# old_line_kick.net
KiCad netlist of a schematic drawn in EAGLE
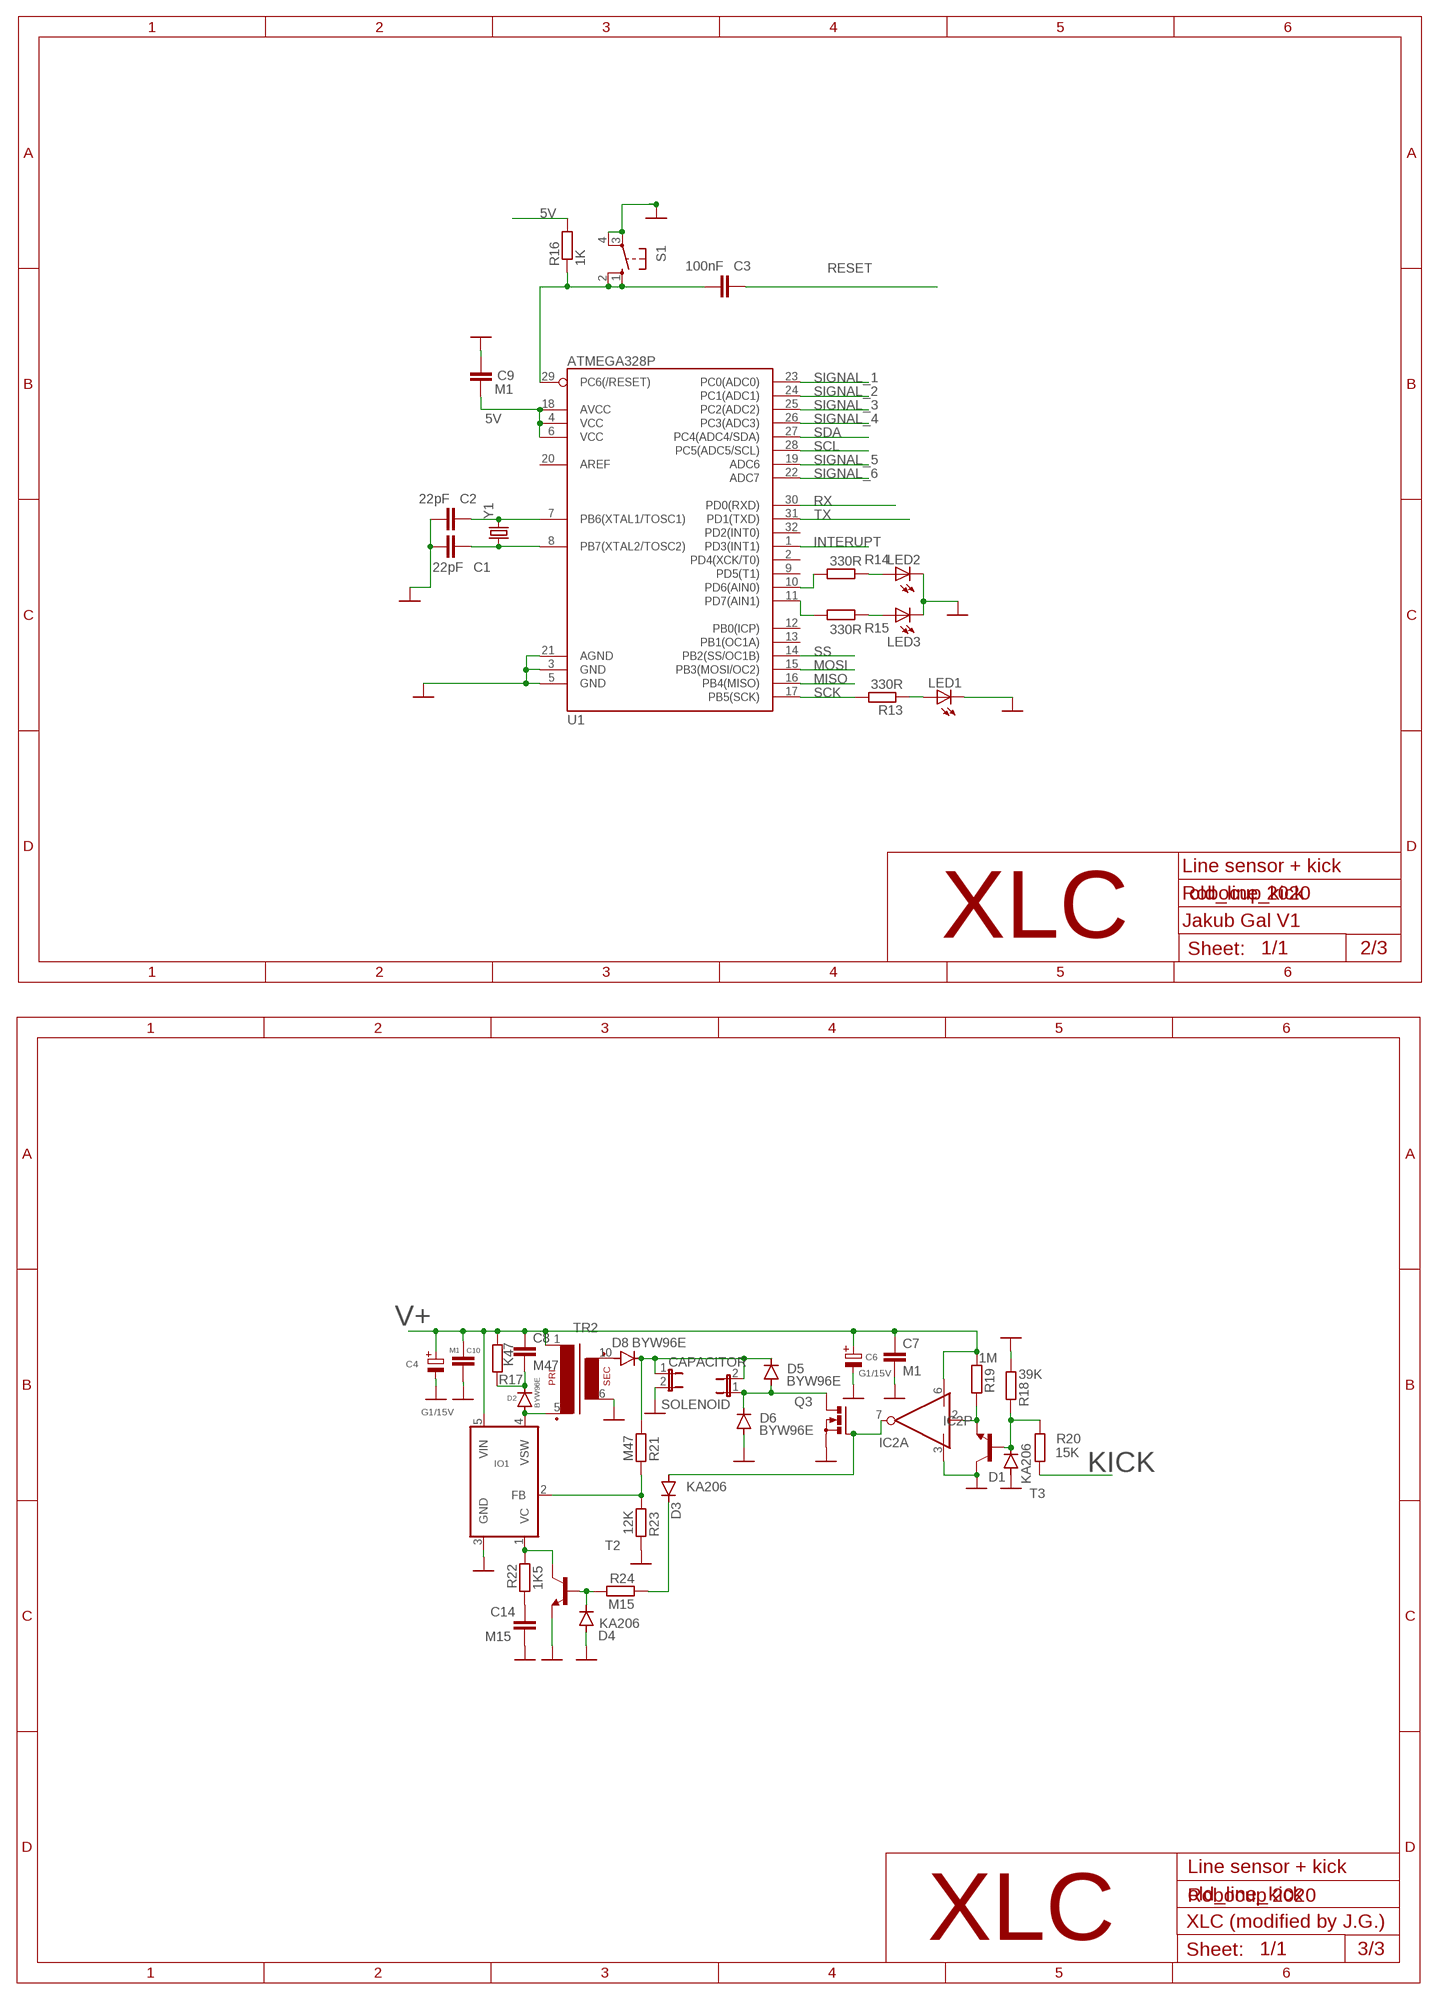
[diagram p0: schematic, sheet 1, part 1 of 2]
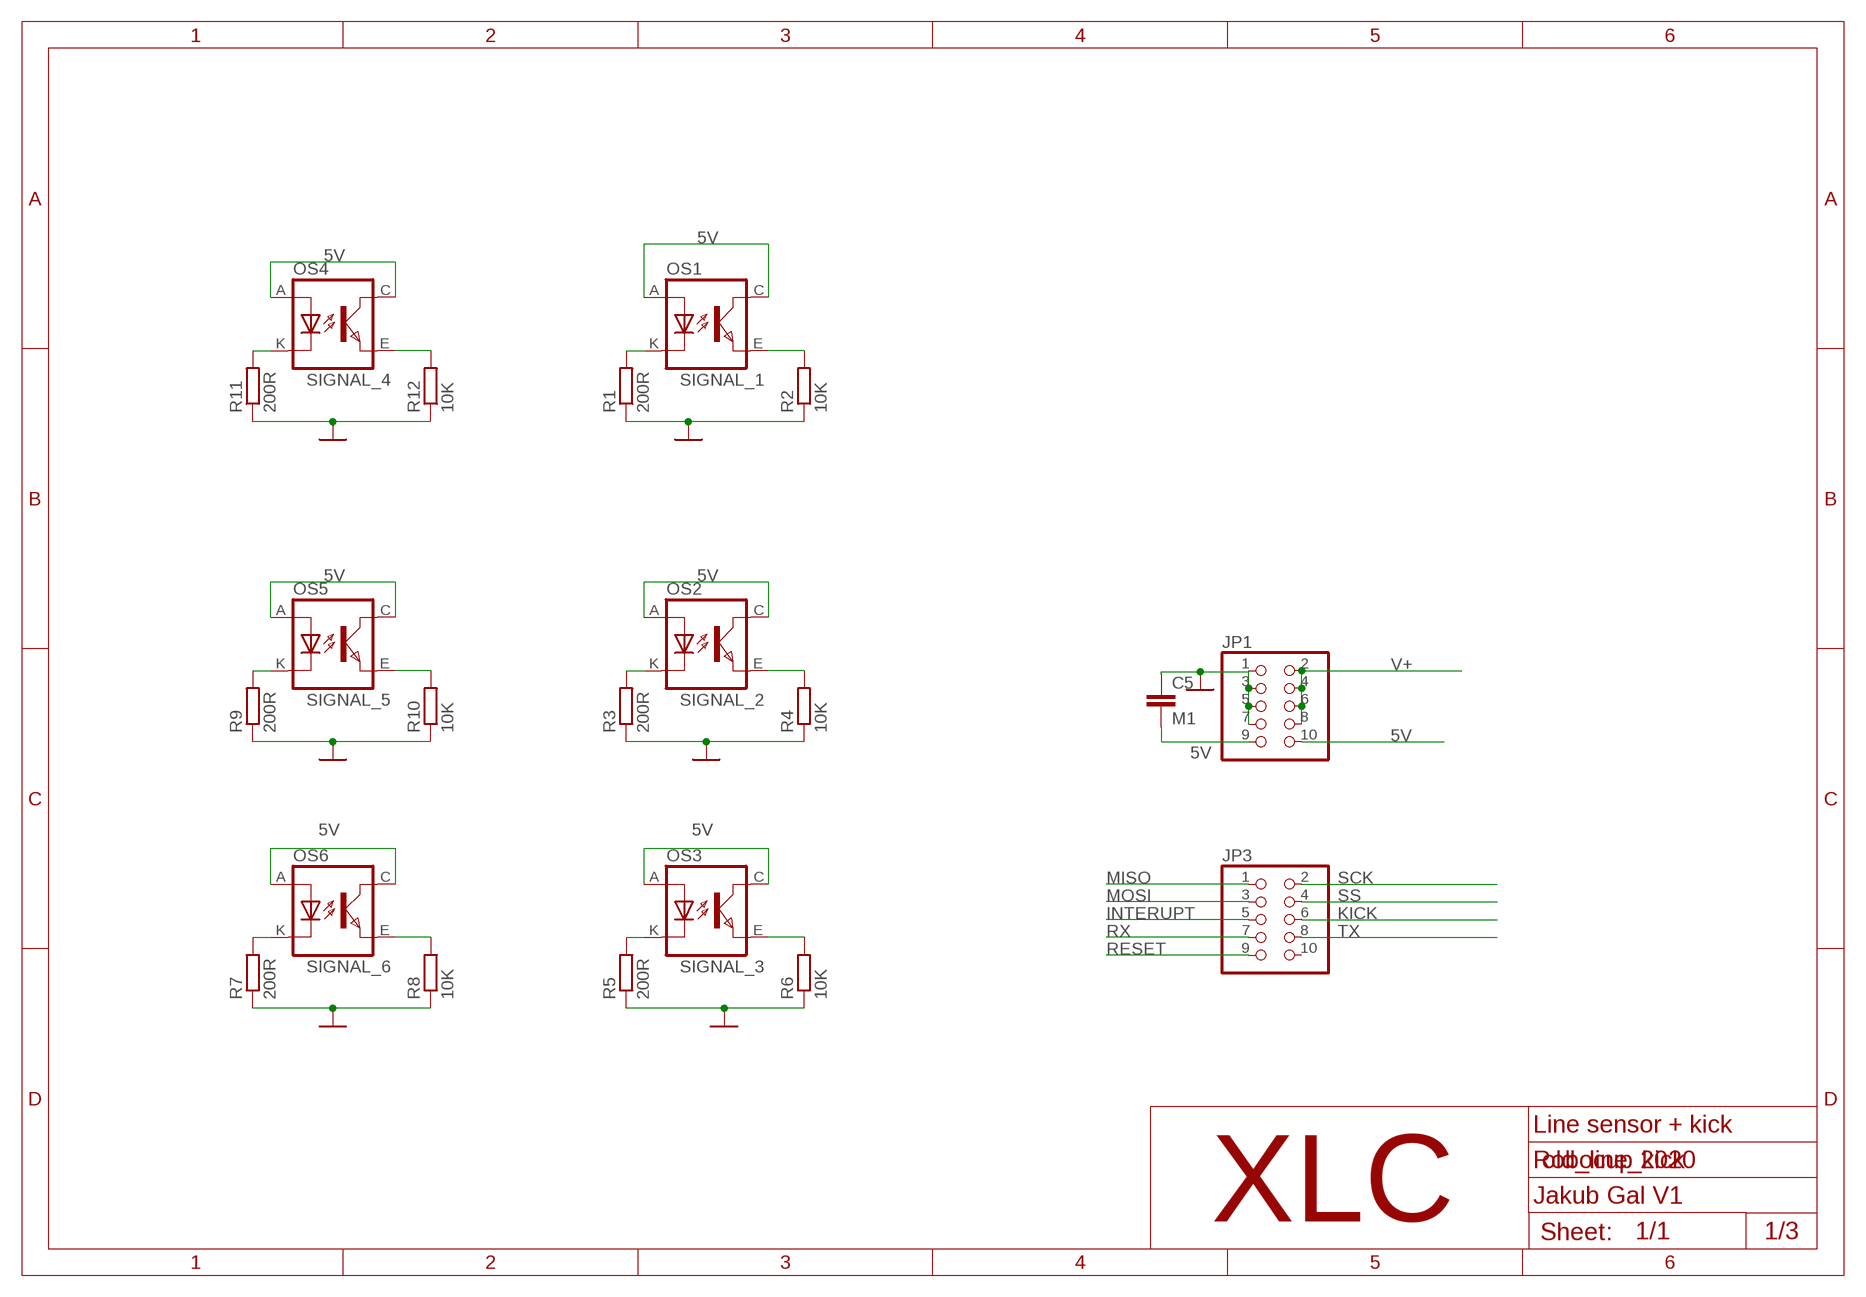
[diagram p1: schematic, sheet 1, part 2 of 2]

(export (version "E")
  (design (tool "Eeschema 10.0.6"))
  (components
    (comp (ref "C1")
      (value "22pF")
      (footprint "eagle-import:C0603")
      (libsource (lib "eagle-import") (part "rcl@1_C-EUC0603"))
    )
    (comp (ref "C2")
      (value "22pF")
      (footprint "eagle-import:C0603")
      (libsource (lib "eagle-import") (part "rcl@1_C-EUC0603"))
    )
    (comp (ref "C3")
      (value "100nF")
      (footprint "eagle-import:C0603")
      (libsource (lib "eagle-import") (part "rcl@1_C-EUC0603"))
    )
    (comp (ref "C4")
      (value "G1/15V")
      (footprint "eagle-import:E-2,5_7-RAD")
      (libsource (lib "eagle-import") (part "KOND-ELEKT-2,5/7"))
    )
    (comp (ref "C5")
      (value "M1")
      (footprint "eagle-import:C0603")
      (libsource (lib "eagle-import") (part "C-EUC0603"))
    )
    (comp (ref "C6")
      (value "G1/15V")
      (footprint "eagle-import:E-2,5_7-RAD")
      (libsource (lib "eagle-import") (part "KOND-ELEKT-2,5/7"))
    )
    (comp (ref "C7")
      (value "M1")
      (footprint "eagle-import:C0805K")
      (libsource (lib "eagle-import") (part "resistor_C-EUC0805K"))
    )
    (comp (ref "C8")
      (value "M47")
      (footprint "eagle-import:C1206K")
      (libsource (lib "eagle-import") (part "C-EUC1206K"))
    )
    (comp (ref "C9")
      (value "M1")
      (footprint "eagle-import:C0603")
      (libsource (lib "eagle-import") (part "rcl@1_C-EUC0603"))
    )
    (comp (ref "C10")
      (value "M1")
      (footprint "eagle-import:C0805K")
      (libsource (lib "eagle-import") (part "resistor_C-EUC0805K"))
    )
    (comp (ref "C14")
      (value "M15")
      (footprint "eagle-import:C0805K")
      (libsource (lib "eagle-import") (part "resistor_C-EUC0805K"))
    )
    (comp (ref "CAPACITOR")
      (value "JP1E")
      (footprint "eagle-import:JP1")
      (libsource (lib "eagle-import") (part "JP1E"))
    )
    (comp (ref "D1")
      (value "KA206")
      (footprint "eagle-import:D-7.5")
      (libsource (lib "eagle-import") (part "DIODE-D-7.5"))
    )
    (comp (ref "D2")
      (value "BYW96E")
      (footprint "eagle-import:SOD64-10")
      (libsource (lib "eagle-import") (part "BYW96"))
    )
    (comp (ref "D3")
      (value "KA206")
      (footprint "eagle-import:D-7.5")
      (libsource (lib "eagle-import") (part "DIODE-D-7.5"))
    )
    (comp (ref "D4")
      (value "KA206")
      (footprint "eagle-import:D-7.5")
      (libsource (lib "eagle-import") (part "DIODE-D-7.5"))
    )
    (comp (ref "D5")
      (value "BYW96E")
      (footprint "eagle-import:SOD64-10")
      (libsource (lib "eagle-import") (part "BYW96"))
    )
    (comp (ref "D6")
      (value "BYW96E")
      (footprint "eagle-import:SOD64-10")
      (libsource (lib "eagle-import") (part "BYW96"))
    )
    (comp (ref "D8")
      (value "BYW96E")
      (footprint "eagle-import:SOD64-10")
      (libsource (lib "eagle-import") (part "BYW96"))
    )
    (comp (ref "IC2")
      (value "MIC4423BM")
      (footprint "eagle-import:SO08")
      (libsource (lib "eagle-import") (part "MIC4423BM"))
    )
    (comp (ref "IO1")
      (value "LT1071V")
      (footprint "eagle-import:TO220-5P")
      (libsource (lib "eagle-import") (part "LT1071V"))
    )
    (comp (ref "JP1")
      (value "PINHD-2X5IDC")
      (footprint "eagle-import:2X05_IDC")
      (libsource (lib "eagle-import") (part "PINHD-2X5IDC"))
    )
    (comp (ref "JP3")
      (value "PINHD-2X5IDC")
      (footprint "eagle-import:2X05_IDC")
      (libsource (lib "eagle-import") (part "PINHD-2X5IDC"))
    )
    (comp (ref "LED1")
      (value "LEDCHIPLED_0603")
      (footprint "eagle-import:CHIPLED_0603")
      (libsource (lib "eagle-import") (part "LEDCHIPLED_0603"))
    )
    (comp (ref "LED2")
      (value "LEDCHIPLED_0603")
      (footprint "eagle-import:CHIPLED_0603")
      (libsource (lib "eagle-import") (part "LEDCHIPLED_0603"))
    )
    (comp (ref "LED3")
      (value "LEDCHIPLED_0603")
      (footprint "eagle-import:CHIPLED_0603")
      (libsource (lib "eagle-import") (part "LEDCHIPLED_0603"))
    )
    (comp (ref "OS1")
      (value "TCRT5000")
      (footprint "eagle-import:TCRT5000")
      (libsource (lib "eagle-import") (part "TCRT5000"))
    )
    (comp (ref "OS2")
      (value "TCRT5000")
      (footprint "eagle-import:TCRT5000")
      (libsource (lib "eagle-import") (part "TCRT5000"))
    )
    (comp (ref "OS3")
      (value "TCRT5000")
      (footprint "eagle-import:TCRT5000")
      (libsource (lib "eagle-import") (part "TCRT5000"))
    )
    (comp (ref "OS4")
      (value "TCRT5000")
      (footprint "eagle-import:TCRT5000")
      (fields (field (name "SPICEPREFIX") "O"))
      (libsource (lib "eagle-import") (part "TCRT5000"))
    )
    (comp (ref "OS5")
      (value "TCRT5000")
      (footprint "eagle-import:TCRT5000")
      (libsource (lib "eagle-import") (part "TCRT5000"))
    )
    (comp (ref "OS6")
      (value "TCRT5000")
      (footprint "eagle-import:TCRT5000")
      (fields (field (name "SPICEPREFIX") "O"))
      (libsource (lib "eagle-import") (part "TCRT5000"))
    )
    (comp (ref "Q3")
      (value "PMOSFET_NTO220BV")
      (footprint "eagle-import:TO220BV")
      (libsource (lib "eagle-import") (part "PMOSFET_NTO220BV"))
    )
    (comp (ref "R1")
      (value "200R")
      (footprint "eagle-import:R0603")
      (libsource (lib "eagle-import") (part "R-EU_R0603"))
    )
    (comp (ref "R2")
      (value "10K")
      (footprint "eagle-import:R0603")
      (libsource (lib "eagle-import") (part "R-EU_R0603"))
    )
    (comp (ref "R3")
      (value "200R")
      (footprint "eagle-import:R0603")
      (libsource (lib "eagle-import") (part "R-EU_R0603"))
    )
    (comp (ref "R4")
      (value "10K")
      (footprint "eagle-import:R0603")
      (libsource (lib "eagle-import") (part "R-EU_R0603"))
    )
    (comp (ref "R5")
      (value "200R")
      (footprint "eagle-import:R0603")
      (libsource (lib "eagle-import") (part "R-EU_R0603"))
    )
    (comp (ref "R6")
      (value "10K")
      (footprint "eagle-import:R0603")
      (libsource (lib "eagle-import") (part "R-EU_R0603"))
    )
    (comp (ref "R7")
      (value "200R")
      (footprint "eagle-import:R0603")
      (libsource (lib "eagle-import") (part "R-EU_R0603"))
    )
    (comp (ref "R8")
      (value "10K")
      (footprint "eagle-import:R0603")
      (libsource (lib "eagle-import") (part "R-EU_R0603"))
    )
    (comp (ref "R9")
      (value "200R")
      (footprint "eagle-import:R0603")
      (libsource (lib "eagle-import") (part "R-EU_R0603"))
    )
    (comp (ref "R10")
      (value "10K")
      (footprint "eagle-import:R0603")
      (libsource (lib "eagle-import") (part "R-EU_R0603"))
    )
    (comp (ref "R11")
      (value "200R")
      (footprint "eagle-import:R0603")
      (libsource (lib "eagle-import") (part "R-EU_R0603"))
    )
    (comp (ref "R12")
      (value "10K")
      (footprint "eagle-import:R0603")
      (libsource (lib "eagle-import") (part "R-EU_R0603"))
    )
    (comp (ref "R13")
      (value "330R")
      (footprint "eagle-import:R0603")
      (libsource (lib "eagle-import") (part "R-EU_R0603"))
    )
    (comp (ref "R14")
      (value "330R")
      (footprint "eagle-import:R0603")
      (libsource (lib "eagle-import") (part "R-EU_R0603"))
    )
    (comp (ref "R15")
      (value "330R")
      (footprint "eagle-import:R0603")
      (libsource (lib "eagle-import") (part "R-EU_R0603"))
    )
    (comp (ref "R16")
      (value "1K")
      (footprint "eagle-import:R0603")
      (libsource (lib "eagle-import") (part "R-EU_R0603"))
    )
    (comp (ref "R17")
      (value "K47")
      (footprint "eagle-import:R0603")
      (libsource (lib "eagle-import") (part "resistor_R-EU_R0603"))
    )
    (comp (ref "R18")
      (value "39K")
      (footprint "eagle-import:R0603")
      (libsource (lib "eagle-import") (part "resistor_R-EU_R0603"))
    )
    (comp (ref "R19")
      (value "1M")
      (footprint "eagle-import:R0603")
      (libsource (lib "eagle-import") (part "resistor_R-EU_R0603"))
    )
    (comp (ref "R20")
      (value "15K")
      (footprint "eagle-import:R0603")
      (libsource (lib "eagle-import") (part "resistor_R-EU_R0603"))
    )
    (comp (ref "R21")
      (value "M47")
      (footprint "eagle-import:R0603")
      (libsource (lib "eagle-import") (part "resistor_R-EU_R0603"))
    )
    (comp (ref "R22")
      (value "1K5")
      (footprint "eagle-import:R0603")
      (libsource (lib "eagle-import") (part "resistor_R-EU_R0603"))
    )
    (comp (ref "R23")
      (value "12K")
      (footprint "eagle-import:R0603")
      (libsource (lib "eagle-import") (part "resistor_R-EU_R0603"))
    )
    (comp (ref "R24")
      (value "M15")
      (footprint "eagle-import:R0603")
      (libsource (lib "eagle-import") (part "resistor_R-EU_R0603"))
    )
    (comp (ref "S1")
      (value "10-XX")
      (footprint "eagle-import:B3F-10XX")
      (fields (field (name "MPN") "B3F-1000"))
      (libsource (lib "eagle-import") (part "10-XX"))
    )
    (comp (ref "SOLENOID")
      (value "JP1E")
      (footprint "eagle-import:JP1")
      (libsource (lib "eagle-import") (part "JP1E"))
    )
    (comp (ref "T2")
      (value "-NPN-SC59-BEC")
      (footprint "eagle-import:SC59-BEC")
      (libsource (lib "eagle-import") (part "-NPN-SC59-BEC"))
    )
    (comp (ref "T3")
      (value "-NPN-SC59-BEC")
      (footprint "eagle-import:SC59-BEC")
      (libsource (lib "eagle-import") (part "-NPN-SC59-BEC"))
    )
    (comp (ref "TR2")
      (value "TRAFO-E10-R\"\"")
      (footprint "eagle-import:TRAFO-EE17X20")
      (libsource (lib "eagle-import") (part "TRAFO-E10-R{dblquote}{dblquote}"))
    )
    (comp (ref "U1")
      (value "ATMEGA328P")
      (footprint "eagle-import:TQFP32-08")
      (libsource (lib "eagle-import") (part "ATMEGA328_SMT"))
    )
    (comp (ref "Y1")
      (value "CRYSTALHC49US")
      (footprint "eagle-import:HC49US")
      (libsource (lib "eagle-import") (part "CRYSTALHC49US"))
    )
  )
  (nets
    (net (code "1") (name "/5V") (class "Default")
      (node (ref "C5") (pin "2") (pinfunction "2_2") (pintype "passive"))
      (node (ref "C9") (pin "1") (pinfunction "1_1") (pintype "passive"))
      (node (ref "JP1") (pin "10") (pinfunction "10_10") (pintype "passive"))
      (node (ref "JP1") (pin "9") (pinfunction "9_9") (pintype "passive"))
      (node (ref "OS1") (pin "A") (pinfunction "ANODE_A") (pintype "passive"))
      (node (ref "OS1") (pin "C") (pinfunction "COLLECTOR_C") (pintype "passive"))
      (node (ref "OS2") (pin "A") (pinfunction "ANODE_A") (pintype "passive"))
      (node (ref "OS2") (pin "C") (pinfunction "COLLECTOR_C") (pintype "passive"))
      (node (ref "OS3") (pin "A") (pinfunction "ANODE_A") (pintype "passive"))
      (node (ref "OS3") (pin "C") (pinfunction "COLLECTOR_C") (pintype "passive"))
      (node (ref "OS4") (pin "A") (pinfunction "ANODE_A") (pintype "passive"))
      (node (ref "OS4") (pin "C") (pinfunction "COLLECTOR_C") (pintype "passive"))
      (node (ref "OS5") (pin "A") (pinfunction "ANODE_A") (pintype "passive"))
      (node (ref "OS5") (pin "C") (pinfunction "COLLECTOR_C") (pintype "passive"))
      (node (ref "OS6") (pin "A") (pinfunction "ANODE_A") (pintype "passive"))
      (node (ref "OS6") (pin "C") (pinfunction "COLLECTOR_C") (pintype "passive"))
      (node (ref "R16") (pin "2") (pinfunction "2_2") (pintype "passive"))
      (node (ref "U1") (pin "18") (pinfunction "AVCC_18") (pintype "bidirectional"))
      (node (ref "U1") (pin "4") (pinfunction "VCC_4") (pintype "bidirectional"))
      (node (ref "U1") (pin "6") (pinfunction "VCC_6") (pintype "bidirectional"))
    )
    (net (code "2") (name "/INTERUPT") (class "Default")
      (node (ref "JP3") (pin "5") (pinfunction "5_5") (pintype "passive"))
      (node (ref "U1") (pin "1") (pinfunction "PD3(INT1)_1") (pintype "bidirectional"))
    )
    (net (code "3") (name "/KICK") (class "Default")
      (node (ref "JP3") (pin "6") (pinfunction "6_6") (pintype "passive"))
      (node (ref "R20") (pin "1") (pinfunction "1_1") (pintype "passive"))
    )
    (net (code "4") (name "/MISO") (class "Default")
      (node (ref "JP3") (pin "1") (pinfunction "1_1") (pintype "passive"))
      (node (ref "U1") (pin "16") (pinfunction "PB4(MISO)_16") (pintype "bidirectional"))
    )
    (net (code "5") (name "/MOSI") (class "Default")
      (node (ref "JP3") (pin "3") (pinfunction "3_3") (pintype "passive"))
      (node (ref "U1") (pin "15") (pinfunction "PB3(MOSI/OC2)_15") (pintype "bidirectional"))
    )
    (net (code "6") (name "/RESET") (class "Default")
      (node (ref "C3") (pin "2") (pinfunction "2_2") (pintype "passive"))
      (node (ref "JP3") (pin "9") (pinfunction "9_9") (pintype "passive"))
    )
    (net (code "7") (name "/RX") (class "Default")
      (node (ref "JP3") (pin "7") (pinfunction "7_7") (pintype "passive"))
      (node (ref "U1") (pin "30") (pinfunction "PD0(RXD)_30") (pintype "bidirectional"))
    )
    (net (code "8") (name "/SCK") (class "Default")
      (node (ref "JP3") (pin "2") (pinfunction "2_2") (pintype "passive"))
      (node (ref "R13") (pin "2") (pinfunction "2_2") (pintype "passive"))
      (node (ref "U1") (pin "17") (pinfunction "PB5(SCK)_17") (pintype "bidirectional"))
    )
    (net (code "9") (name "/SCL") (class "Default")
      (node (ref "U1") (pin "28") (pinfunction "PC5(ADC5/SCL)_28") (pintype "bidirectional"))
    )
    (net (code "10") (name "/SDA") (class "Default")
      (node (ref "U1") (pin "27") (pinfunction "PC4(ADC4/SDA)_27") (pintype "bidirectional"))
    )
    (net (code "11") (name "/SIGNAL_1") (class "Default")
      (node (ref "OS1") (pin "E") (pinfunction "EMITTER_E") (pintype "passive"))
      (node (ref "R2") (pin "2") (pinfunction "2_2") (pintype "passive"))
      (node (ref "U1") (pin "23") (pinfunction "PC0(ADC0)_23") (pintype "bidirectional"))
    )
    (net (code "12") (name "/SIGNAL_2") (class "Default")
      (node (ref "OS2") (pin "E") (pinfunction "EMITTER_E") (pintype "passive"))
      (node (ref "R4") (pin "2") (pinfunction "2_2") (pintype "passive"))
      (node (ref "U1") (pin "24") (pinfunction "PC1(ADC1)_24") (pintype "bidirectional"))
    )
    (net (code "13") (name "/SIGNAL_3") (class "Default")
      (node (ref "OS3") (pin "E") (pinfunction "EMITTER_E") (pintype "passive"))
      (node (ref "R6") (pin "2") (pinfunction "2_2") (pintype "passive"))
      (node (ref "U1") (pin "25") (pinfunction "PC2(ADC2)_25") (pintype "bidirectional"))
    )
    (net (code "14") (name "/SIGNAL_4") (class "Default")
      (node (ref "OS4") (pin "E") (pinfunction "EMITTER_E") (pintype "passive"))
      (node (ref "R12") (pin "2") (pinfunction "2_2") (pintype "passive"))
      (node (ref "U1") (pin "26") (pinfunction "PC3(ADC3)_26") (pintype "bidirectional"))
    )
    (net (code "15") (name "/SIGNAL_5") (class "Default")
      (node (ref "OS5") (pin "E") (pinfunction "EMITTER_E") (pintype "passive"))
      (node (ref "R10") (pin "2") (pinfunction "2_2") (pintype "passive"))
      (node (ref "U1") (pin "19") (pinfunction "ADC6_19") (pintype "bidirectional"))
    )
    (net (code "16") (name "/SIGNAL_6") (class "Default")
      (node (ref "OS6") (pin "E") (pinfunction "EMITTER_E") (pintype "passive"))
      (node (ref "R8") (pin "2") (pinfunction "2_2") (pintype "passive"))
      (node (ref "U1") (pin "22") (pinfunction "ADC7_22") (pintype "bidirectional"))
    )
    (net (code "17") (name "/SS") (class "Default")
      (node (ref "JP3") (pin "4") (pinfunction "4_4") (pintype "passive"))
      (node (ref "U1") (pin "14") (pinfunction "PB2(SS/OC1B)_14") (pintype "bidirectional"))
    )
    (net (code "18") (name "/TX") (class "Default")
      (node (ref "JP3") (pin "8") (pinfunction "8_8") (pintype "passive"))
      (node (ref "U1") (pin "31") (pinfunction "PD1(TXD)_31") (pintype "bidirectional"))
    )
    (net (code "19") (name "/V+") (class "Default")
      (node (ref "C10") (pin "1") (pinfunction "1_1") (pintype "passive"))
      (node (ref "C4") (pin "+") (pinfunction "+_+") (pintype "passive"))
      (node (ref "C6") (pin "+") (pinfunction "+_+") (pintype "passive"))
      (node (ref "C7") (pin "1") (pinfunction "1_1") (pintype "passive"))
      (node (ref "C8") (pin "1") (pinfunction "1_1") (pintype "passive"))
      (node (ref "IC2") (pin "6") (pinfunction "V+_6") (pintype "power_in"))
      (node (ref "IO1") (pin "5") (pinfunction "VIN_5") (pintype "power_in"))
      (node (ref "JP1") (pin "2") (pinfunction "2_2") (pintype "passive"))
      (node (ref "JP1") (pin "4") (pinfunction "4_4") (pintype "passive"))
      (node (ref "JP1") (pin "6") (pinfunction "6_6") (pintype "passive"))
      (node (ref "JP1") (pin "8") (pinfunction "8_8") (pintype "passive"))
      (node (ref "R17") (pin "1") (pinfunction "1_1") (pintype "passive"))
      (node (ref "R19") (pin "2") (pinfunction "2_2") (pintype "passive"))
      (node (ref "TR2") (pin "1") (pinfunction "1_1") (pintype "passive"))
    )
    (net (code "20") (name "GND") (class "Default")
      (node (ref "C1") (pin "1") (pinfunction "1_1") (pintype "passive"))
      (node (ref "C10") (pin "2") (pinfunction "2_2") (pintype "passive"))
      (node (ref "C14") (pin "2") (pinfunction "2_2") (pintype "passive"))
      (node (ref "C2") (pin "1") (pinfunction "1_1") (pintype "passive"))
      (node (ref "C4") (pin "-") (pinfunction "-_-") (pintype "passive"))
      (node (ref "C5") (pin "1") (pinfunction "1_1") (pintype "passive"))
      (node (ref "C6") (pin "-") (pinfunction "-_-") (pintype "passive"))
      (node (ref "C7") (pin "2") (pinfunction "2_2") (pintype "passive"))
      (node (ref "C9") (pin "2") (pinfunction "2_2") (pintype "passive"))
      (node (ref "CAPACITOR") (pin "2") (pinfunction "2_2") (pintype "passive"))
      (node (ref "D1") (pin "A") (pinfunction "A_A") (pintype "passive"))
      (node (ref "D4") (pin "A") (pinfunction "A_A") (pintype "passive"))
      (node (ref "D6") (pin "A") (pinfunction "A_A") (pintype "passive"))
      (node (ref "IC2") (pin "3") (pinfunction "GND_3") (pintype "power_in"))
      (node (ref "IO1") (pin "3") (pinfunction "GND_3") (pintype "power_in"))
      (node (ref "JP1") (pin "1") (pinfunction "1_1") (pintype "passive"))
      (node (ref "JP1") (pin "3") (pinfunction "3_3") (pintype "passive"))
      (node (ref "JP1") (pin "5") (pinfunction "5_5") (pintype "passive"))
      (node (ref "JP1") (pin "7") (pinfunction "7_7") (pintype "passive"))
      (node (ref "LED1") (pin "C") (pinfunction "C_C") (pintype "passive"))
      (node (ref "LED2") (pin "C") (pinfunction "C_C") (pintype "passive"))
      (node (ref "LED3") (pin "C") (pinfunction "C_C") (pintype "passive"))
      (node (ref "Q3") (pin "S") (pinfunction "S_S") (pintype "passive"))
      (node (ref "R1") (pin "1") (pinfunction "1_1") (pintype "passive"))
      (node (ref "R10") (pin "1") (pinfunction "1_1") (pintype "passive"))
      (node (ref "R11") (pin "1") (pinfunction "1_1") (pintype "passive"))
      (node (ref "R12") (pin "1") (pinfunction "1_1") (pintype "passive"))
      (node (ref "R18") (pin "2") (pinfunction "2_2") (pintype "passive"))
      (node (ref "R2") (pin "1") (pinfunction "1_1") (pintype "passive"))
      (node (ref "R23") (pin "1") (pinfunction "1_1") (pintype "passive"))
      (node (ref "R3") (pin "1") (pinfunction "1_1") (pintype "passive"))
      (node (ref "R4") (pin "1") (pinfunction "1_1") (pintype "passive"))
      (node (ref "R5") (pin "1") (pinfunction "1_1") (pintype "passive"))
      (node (ref "R6") (pin "1") (pinfunction "1_1") (pintype "passive"))
      (node (ref "R7") (pin "1") (pinfunction "1_1") (pintype "passive"))
      (node (ref "R8") (pin "1") (pinfunction "1_1") (pintype "passive"))
      (node (ref "R9") (pin "1") (pinfunction "1_1") (pintype "passive"))
      (node (ref "S1") (pin "3") (pinfunction "P_3") (pintype "passive"))
      (node (ref "S1") (pin "4") (pinfunction "P1_4") (pintype "passive"))
      (node (ref "T2") (pin "E") (pinfunction "E_E") (pintype "passive"))
      (node (ref "T3") (pin "C") (pinfunction "C_C") (pintype "passive"))
      (node (ref "TR2") (pin "6") (pinfunction "3_6") (pintype "passive"))
      (node (ref "U1") (pin "21") (pinfunction "AGND_21") (pintype "bidirectional"))
      (node (ref "U1") (pin "3") (pinfunction "GND_3") (pintype "bidirectional"))
      (node (ref "U1") (pin "5") (pinfunction "GND_5") (pintype "bidirectional"))
    )
    (net (code "21") (name "Net-(C8-Pad2)") (class "Default")
      (node (ref "C8") (pin "2") (pinfunction "2_2") (pintype "passive"))
      (node (ref "D2") (pin "C") (pinfunction "C_C") (pintype "passive"))
      (node (ref "R17") (pin "2") (pinfunction "2_2") (pintype "passive"))
    )
    (net (code "22") (name "Net-(C14-Pad1)") (class "Default")
      (node (ref "C14") (pin "1") (pinfunction "1_1") (pintype "passive"))
      (node (ref "R22") (pin "2") (pinfunction "2_2") (pintype "passive"))
    )
    (net (code "23") (name "Net-(CAPACITOR-Pad1)") (class "Default")
      (node (ref "CAPACITOR") (pin "1") (pinfunction "1_1") (pintype "passive"))
      (node (ref "D5") (pin "C") (pinfunction "C_C") (pintype "passive"))
      (node (ref "D8") (pin "C") (pinfunction "C_C") (pintype "passive"))
      (node (ref "R21") (pin "2") (pinfunction "2_2") (pintype "passive"))
      (node (ref "SOLENOID") (pin "2") (pinfunction "2_2") (pintype "passive"))
    )
    (net (code "24") (name "Net-(D1-PadC)") (class "Default")
      (node (ref "D1") (pin "C") (pinfunction "C_C") (pintype "passive"))
      (node (ref "R18") (pin "1") (pinfunction "1_1") (pintype "passive"))
      (node (ref "R20") (pin "2") (pinfunction "2_2") (pintype "passive"))
      (node (ref "T3") (pin "B") (pinfunction "B_B") (pintype "passive"))
    )
    (net (code "25") (name "Net-(D3-PadC)") (class "Default")
      (node (ref "D3") (pin "C") (pinfunction "C_C") (pintype "passive"))
      (node (ref "R24") (pin "1") (pinfunction "1_1") (pintype "passive"))
    )
    (net (code "26") (name "Net-(D4-PadC)") (class "Default")
      (node (ref "D4") (pin "C") (pinfunction "C_C") (pintype "passive"))
      (node (ref "R24") (pin "2") (pinfunction "2_2") (pintype "passive"))
      (node (ref "T2") (pin "B") (pinfunction "B_B") (pintype "passive"))
    )
    (net (code "27") (name "Net-(D5-PadA)") (class "Default")
      (node (ref "D5") (pin "A") (pinfunction "A_A") (pintype "passive"))
      (node (ref "D6") (pin "C") (pinfunction "C_C") (pintype "passive"))
      (node (ref "Q3") (pin "D") (pinfunction "D_D") (pintype "passive"))
      (node (ref "SOLENOID") (pin "1") (pinfunction "1_1") (pintype "passive"))
    )
    (net (code "28") (name "Net-(IC2A-IN)") (class "Default")
      (node (ref "IC2") (pin "2") (pinfunction "IN_2") (pintype "input"))
      (node (ref "R19") (pin "1") (pinfunction "1_1") (pintype "passive"))
      (node (ref "T3") (pin "E") (pinfunction "E_E") (pintype "passive"))
    )
    (net (code "29") (name "Net-(IC2A-OUT)") (class "Default")
      (node (ref "D3") (pin "A") (pinfunction "A_A") (pintype "passive"))
      (node (ref "IC2") (pin "7") (pinfunction "OUT_7") (pintype "output"))
      (node (ref "Q3") (pin "G") (pinfunction "G_G") (pintype "passive"))
    )
    (net (code "30") (name "Net-(IO1-FB)") (class "Default")
      (node (ref "IO1") (pin "2") (pinfunction "FB_2") (pintype "input"))
      (node (ref "R21") (pin "1") (pinfunction "1_1") (pintype "passive"))
      (node (ref "R23") (pin "2") (pinfunction "2_2") (pintype "passive"))
    )
    (net (code "31") (name "Net-(IO1-VC)") (class "Default")
      (node (ref "IO1") (pin "1") (pinfunction "VC_1") (pintype "input"))
      (node (ref "R22") (pin "1") (pinfunction "1_1") (pintype "passive"))
      (node (ref "T2") (pin "C") (pinfunction "C_C") (pintype "passive"))
    )
    (net (code "32") (name "Net-(IO1-VSW)") (class "Default")
      (node (ref "D2") (pin "A") (pinfunction "A_A") (pintype "passive"))
      (node (ref "IO1") (pin "4") (pinfunction "VSW_4") (pintype "output"))
      (node (ref "TR2") (pin "5") (pinfunction "2_5") (pintype "passive"))
    )
    (net (code "33") (name "Net-(LED1-PadA)") (class "Default")
      (node (ref "LED1") (pin "A") (pinfunction "A_A") (pintype "passive"))
      (node (ref "R13") (pin "1") (pinfunction "1_1") (pintype "passive"))
    )
    (net (code "34") (name "Net-(LED2-PadA)") (class "Default")
      (node (ref "LED2") (pin "A") (pinfunction "A_A") (pintype "passive"))
      (node (ref "R14") (pin "1") (pinfunction "1_1") (pintype "passive"))
    )
    (net (code "35") (name "Net-(LED3-PadA)") (class "Default")
      (node (ref "LED3") (pin "A") (pinfunction "A_A") (pintype "passive"))
      (node (ref "R15") (pin "1") (pinfunction "1_1") (pintype "passive"))
    )
    (net (code "36") (name "Net-(OS1-CATHODE)") (class "Default")
      (node (ref "OS1") (pin "K") (pinfunction "CATHODE_K") (pintype "passive"))
      (node (ref "R1") (pin "2") (pinfunction "2_2") (pintype "passive"))
    )
    (net (code "37") (name "Net-(OS2-CATHODE)") (class "Default")
      (node (ref "OS2") (pin "K") (pinfunction "CATHODE_K") (pintype "passive"))
      (node (ref "R3") (pin "2") (pinfunction "2_2") (pintype "passive"))
    )
    (net (code "38") (name "Net-(OS3-CATHODE)") (class "Default")
      (node (ref "OS3") (pin "K") (pinfunction "CATHODE_K") (pintype "passive"))
      (node (ref "R5") (pin "2") (pinfunction "2_2") (pintype "passive"))
    )
    (net (code "39") (name "Net-(OS4-CATHODE)") (class "Default")
      (node (ref "OS4") (pin "K") (pinfunction "CATHODE_K") (pintype "passive"))
      (node (ref "R11") (pin "2") (pinfunction "2_2") (pintype "passive"))
    )
    (net (code "40") (name "Net-(OS5-CATHODE)") (class "Default")
      (node (ref "OS5") (pin "K") (pinfunction "CATHODE_K") (pintype "passive"))
      (node (ref "R9") (pin "2") (pinfunction "2_2") (pintype "passive"))
    )
    (net (code "41") (name "Net-(OS6-CATHODE)") (class "Default")
      (node (ref "OS6") (pin "K") (pinfunction "CATHODE_K") (pintype "passive"))
      (node (ref "R7") (pin "2") (pinfunction "2_2") (pintype "passive"))
    )
    (net (code "42") (name "Net-(S1-S)") (class "Default")
      (node (ref "C3") (pin "1") (pinfunction "1_1") (pintype "passive"))
      (node (ref "R16") (pin "1") (pinfunction "1_1") (pintype "passive"))
      (node (ref "S1") (pin "1") (pinfunction "S_1") (pintype "passive"))
      (node (ref "S1") (pin "2") (pinfunction "S1_2") (pintype "passive"))
      (node (ref "U1") (pin "29") (pinfunction "PC6(/RESET)_29") (pintype "bidirectional"))
    )
    (net (code "43") (name "Net-(TR2-4)") (class "Default")
      (node (ref "D8") (pin "A") (pinfunction "A_A") (pintype "passive"))
      (node (ref "TR2") (pin "10") (pinfunction "4_10") (pintype "passive"))
    )
    (net (code "44") (name "Net-(U1-PB6(XTAL1{slash}TOSC1))") (class "Default")
      (node (ref "C2") (pin "2") (pinfunction "2_2") (pintype "passive"))
      (node (ref "U1") (pin "7") (pinfunction "PB6(XTAL1/TOSC1)_7") (pintype "bidirectional"))
      (node (ref "Y1") (pin "2") (pinfunction "2_2") (pintype "passive"))
    )
    (net (code "45") (name "Net-(U1-PB7(XTAL2{slash}TOSC2))") (class "Default")
      (node (ref "C1") (pin "2") (pinfunction "2_2") (pintype "passive"))
      (node (ref "U1") (pin "8") (pinfunction "PB7(XTAL2/TOSC2)_8") (pintype "bidirectional"))
      (node (ref "Y1") (pin "1") (pinfunction "1_1") (pintype "passive"))
    )
    (net (code "46") (name "Net-(U1-PD6(AIN0))") (class "Default")
      (node (ref "R14") (pin "2") (pinfunction "2_2") (pintype "passive"))
      (node (ref "U1") (pin "10") (pinfunction "PD6(AIN0)_10") (pintype "bidirectional"))
    )
    (net (code "47") (name "Net-(U1-PD7(AIN1))") (class "Default")
      (node (ref "R15") (pin "2") (pinfunction "2_2") (pintype "passive"))
      (node (ref "U1") (pin "11") (pinfunction "PD7(AIN1)_11") (pintype "bidirectional"))
    )
    (net (code "48") (name "unconnected-(JP3-Pad10)") (class "Default")
      (node (ref "JP3") (pin "10") (pinfunction "10_10") (pintype "passive"))
    )
    (net (code "49") (name "unconnected-(U1-AREF-Pad20)") (class "Default")
      (node (ref "U1") (pin "20") (pinfunction "AREF_20") (pintype "bidirectional"))
    )
    (net (code "50") (name "unconnected-(U1-PB0(ICP)-Pad12)") (class "Default")
      (node (ref "U1") (pin "12") (pinfunction "PB0(ICP)_12") (pintype "bidirectional"))
    )
    (net (code "51") (name "unconnected-(U1-PB1(OC1A)-Pad13)") (class "Default")
      (node (ref "U1") (pin "13") (pinfunction "PB1(OC1A)_13") (pintype "bidirectional"))
    )
    (net (code "52") (name "unconnected-(U1-PD2(INT0)-Pad32)") (class "Default")
      (node (ref "U1") (pin "32") (pinfunction "PD2(INT0)_32") (pintype "bidirectional"))
    )
    (net (code "53") (name "unconnected-(U1-PD4(XCK{slash}T0)-Pad2)") (class "Default")
      (node (ref "U1") (pin "2") (pinfunction "PD4(XCK/T0)_2") (pintype "bidirectional"))
    )
    (net (code "54") (name "unconnected-(U1-PD5(T1)-Pad9)") (class "Default")
      (node (ref "U1") (pin "9") (pinfunction "PD5(T1)_9") (pintype "bidirectional"))
    )
  )
)
